# Power_Sheet.net
KiCad netlist of a schematic drawn in Altium Designer
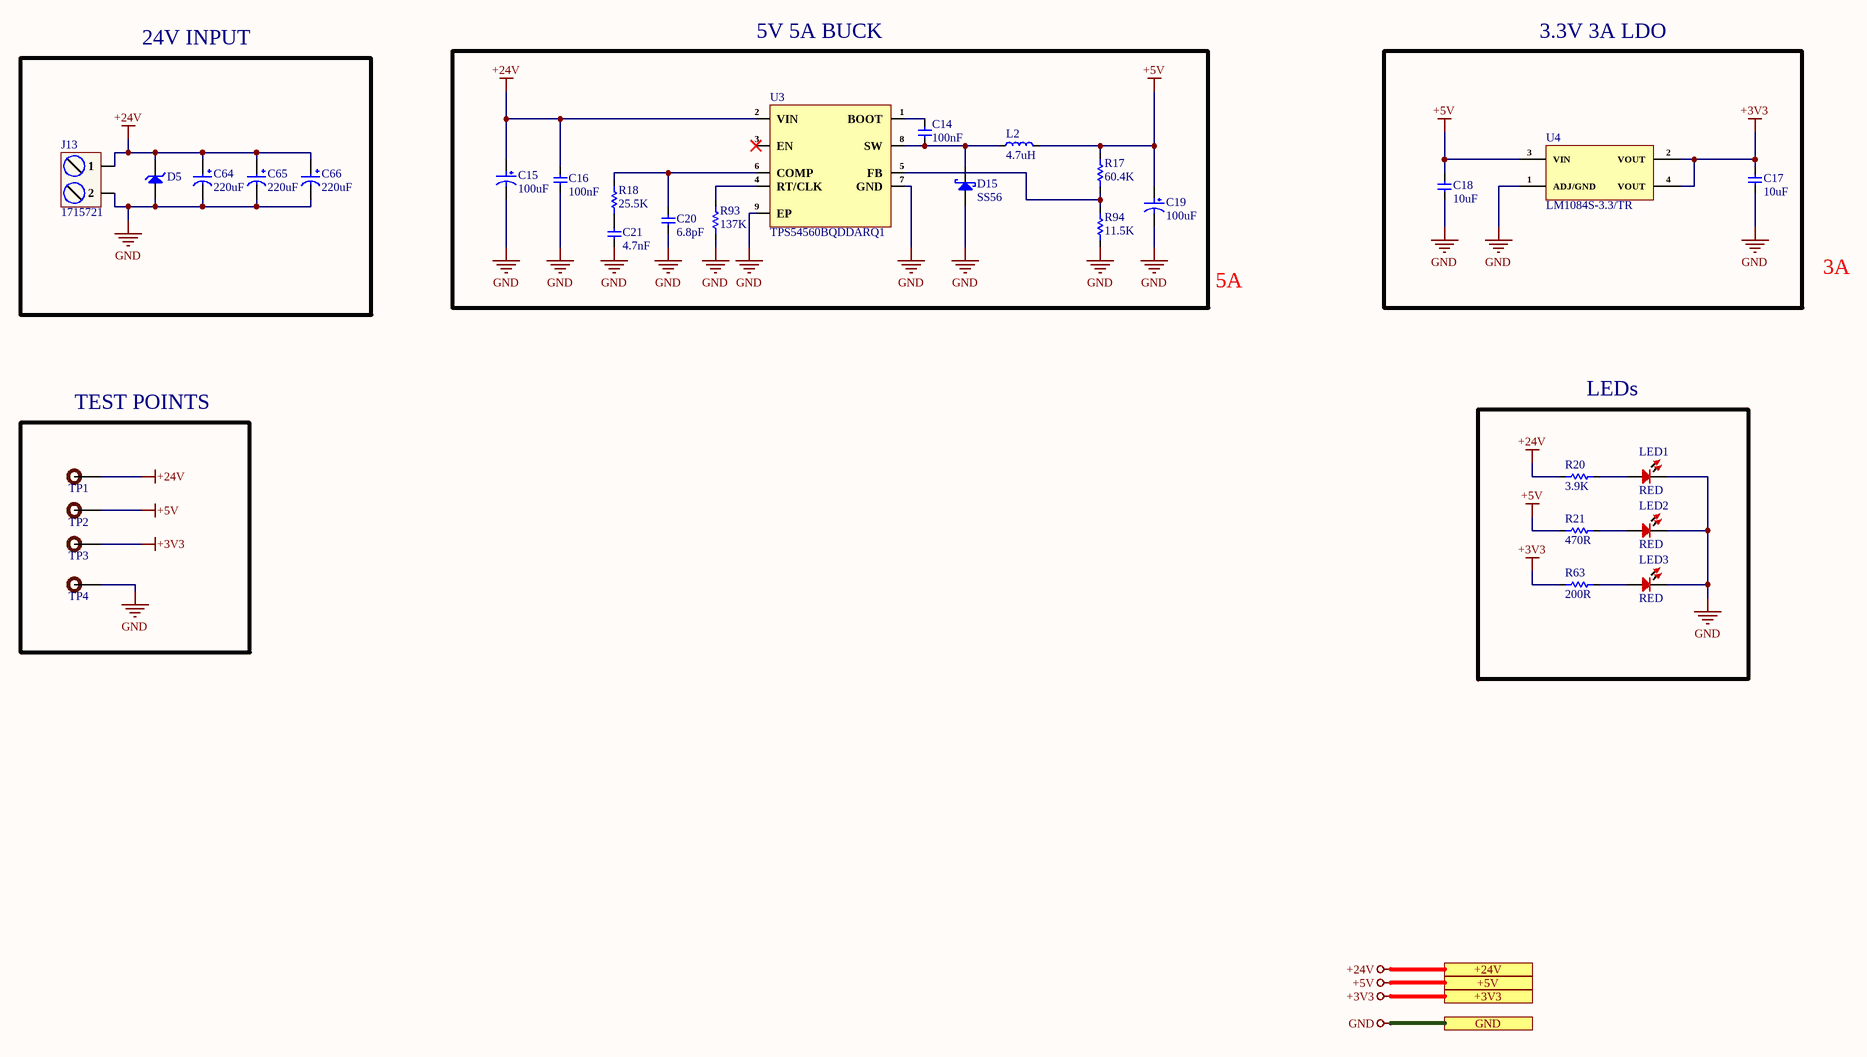
[diagram p0: Power_Sheet.SchDoc]

(export (version "E")
  (design (tool "Eeschema 10.0.6"))
  (components
    (comp (ref "C14")
      (value "100nF")
      (footprint "cap-0402")
      (description "CAP CER 0.1UF 50V X7R 0402")
      (fields
        (field (name "MANUFACTURER") "TDK")
        (field (name "MANUFACTURER PART NUMBER") "C1005X7R1H104KT000F")
      )
      (libsource (lib "eSpark Libraries") (part "C1005X7R1H104KT000F"))
    )
    (comp (ref "C15")
      (value "100uF")
      (footprint "RVT1A101M0605")
      (description "100uF 10V 55mA@120Hz ±20% SMD,D6.3xL5.4mm Aluminum Electrolytic Capacitors - SMD ROHS")
      (fields
        (field (name "MANUFACTURER") "ROQANG")
        (field (name "MANUFACTURER PART NUMBER") "RVT1A101M0605")
      )
      (libsource (lib "eSpark Libraries") (part "RVT1A101M0605"))
    )
    (comp (ref "C16")
      (value "100nF")
      (footprint "cap-0402")
      (description "CAP CER 0.1UF 50V X7R 0402")
      (fields
        (field (name "MANUFACTURER") "TDK")
        (field (name "MANUFACTURER PART NUMBER") "C1005X7R1H104KT000F")
      )
      (libsource (lib "eSpark Libraries") (part "C1005X7R1H104KT000F"))
    )
    (comp (ref "C17")
      (value "10uF")
      (footprint "Cap-0603")
      (description "CAP CER 10UF 25V X5R 0603")
      (fields
        (field (name "MANUFACTURER") "TDK")
        (field (name "MANUFACTURER PART NUMBER") "C1608X5R1E106M080AC")
      )
      (libsource (lib "eSpark Libraries") (part "C1608X5R1E106M080AC"))
    )
    (comp (ref "C18")
      (value "10uF")
      (footprint "Cap-0603")
      (description "CAP CER 10UF 25V X5R 0603")
      (fields
        (field (name "MANUFACTURER") "TDK")
        (field (name "MANUFACTURER PART NUMBER") "C1608X5R1E106M080AC")
      )
      (libsource (lib "eSpark Libraries") (part "C1608X5R1E106M080AC"))
    )
    (comp (ref "C19")
      (value "100uF")
      (footprint "RVT1A101M0605")
      (description "100uF 10V 55mA@120Hz ±20% SMD,D6.3xL5.4mm Aluminum Electrolytic Capacitors - SMD ROHS")
      (fields
        (field (name "MANUFACTURER") "ROQANG")
        (field (name "MANUFACTURER PART NUMBER") "RVT1A101M0605")
      )
      (libsource (lib "eSpark Libraries") (part "RVT1A101M0605"))
    )
    (comp (ref "C20")
      (value "6.8pF")
      (footprint "Cap-0402")
      (description "CAP CER 6.8PF 50V C0G/NPO 0402")
      (fields
        (field (name "MANUFACTURER") "Yageo")
        (field (name "MANUFACTURER PART NUMBER") "CC0402CRNPO9BN6R8")
      )
      (libsource (lib "eSpark Libraries") (part "CC0402CRNPO9BN6R8"))
    )
    (comp (ref "C21")
      (value "4.7nF")
      (footprint "Cap-0402")
      (description "CAP CER 4700PF 50V X7R 0402")
      (fields
        (field (name "MANUFACTURER") "Yageo")
        (field (name "MANUFACTURER PART NUMBER") "CC0402KRX7R9BB472")
      )
      (libsource (lib "eSpark Libraries") (part "CC0402KRX7R9BB472"))
    )
    (comp (ref "C64")
      (value "220uF")
      (footprint "UCD-220uF-10mmDia")
      (description "CAP ALUM 220UF 20% 50V SMD")
      (fields
        (field (name "MANUFACTURER") "Nichicon")
        (field (name "MANUFACTURER PART NUMBER") "UCD1H221MNL1GS")
      )
      (libsource (lib "eSpark Libraries") (part "UCD1H221MNL1GS"))
    )
    (comp (ref "C65")
      (value "220uF")
      (footprint "UCD-220uF-10mmDia")
      (description "CAP ALUM 220UF 20% 50V SMD")
      (fields
        (field (name "MANUFACTURER") "Nichicon")
        (field (name "MANUFACTURER PART NUMBER") "UCD1H221MNL1GS")
      )
      (libsource (lib "eSpark Libraries") (part "UCD1H221MNL1GS"))
    )
    (comp (ref "C66")
      (value "220uF")
      (footprint "UCD-220uF-10mmDia")
      (description "CAP ALUM 220UF 20% 50V SMD")
      (fields
        (field (name "MANUFACTURER") "Nichicon")
        (field (name "MANUFACTURER PART NUMBER") "UCD1H221MNL1GS")
      )
      (libsource (lib "eSpark Libraries") (part "UCD1H221MNL1GS"))
    )
    (comp (ref "D5")
      (value "SMBJ28A-13-F")
      (footprint "SMB_")
      (description "TVS DIODE 28VWM 45.4VC SMB")
      (fields (field (name "MANUFACTURER") "Diodes"))
      (libsource (lib "eSpark Libraries") (part "SMBJ28A-13-F"))
    )
    (comp (ref "D15")
      (value "SS56")
      (footprint "SMA")
      (description "DIODE SCHOTTKY 60V 5A SMA")
      (fields (field (name "MANUFACTURER") "MDD"))
      (libsource (lib "eSpark Libraries") (part "SS56"))
    )
    (comp (ref "J13")
      (value "1715721")
      (footprint "1715721")
      (description "TERM BLK 2P SIDE ENT 5.08MM PCB")
      (fields (field (name "MANUFACTURER") "Phoenix Contact"))
      (libsource (lib "eSpark Libraries") (part "1715721"))
    )
    (comp (ref "L2")
      (value "4.7uH")
      (footprint "YSPI1050-4R7M")
      (description "8A 4.7uH ±20% SMD,10x10.1mm Power Inductors ROHS")
      (fields
        (field (name "MANUFACTURER") "YJYCOIN")
        (field (name "MANUFACTURER PART NUMBER") "YSPI1050-4R7M")
      )
      (libsource (lib "eSpark Libraries") (part "YSPI1050-4R7M"))
    )
    (comp (ref "LED1")
      (value "RED")
      (footprint "LED-0603")
      (description "RED LED 0603 Light Emitting Diodes")
      (fields
        (field (name "MANUFACTURER") "Foshan NationStar Optoelectronics")
        (field (name "MANUFACTURER PART NUMBER") "NCD0603R3")
      )
      (libsource (lib "eSpark Libraries") (part "NCD0603R3"))
    )
    (comp (ref "LED2")
      (value "RED")
      (footprint "LED-0603")
      (description "RED LED 0603 Light Emitting Diodes")
      (fields
        (field (name "MANUFACTURER") "Foshan NationStar Optoelectronics")
        (field (name "MANUFACTURER PART NUMBER") "NCD0603R3")
      )
      (libsource (lib "eSpark Libraries") (part "NCD0603R3"))
    )
    (comp (ref "LED3")
      (value "RED")
      (footprint "LED-0603")
      (description "RED LED 0603 Light Emitting Diodes")
      (fields
        (field (name "MANUFACTURER") "Foshan NationStar Optoelectronics")
        (field (name "MANUFACTURER PART NUMBER") "NCD0603R3")
      )
      (libsource (lib "eSpark Libraries") (part "NCD0603R3"))
    )
    (comp (ref "R17")
      (value "60.4K")
      (footprint "Res-0402")
      (description "60.4kΩ 50V 62.5mW Thick Film Resistors ±1% 0402 Chip Resistor - Surface Mount ROHS")
      (fields (field (name "MANUFACTURER") "VO") (field (name "MANUFACTURER PART NUMBER") "SCR0402F60K4"))
      (libsource (lib "eSpark Libraries") (part "SCR0402F60K4"))
    )
    (comp (ref "R18")
      (value "25.5K")
      (footprint "Res-0402")
      (description "62.5mW Thick Film Resistors 50V ±100ppm/℃ ±1% 25.5kΩ 0402 Chip Resistor - Surface Mount ROHS")
      (fields
        (field (name "LCSC PART NUMBER") "C26970")
        (field (name "MANUFACTURER") "Royal Electronic Factory")
      )
      (libsource (lib "eSpark Libraries") (part "0402WGF2552TCE"))
    )
    (comp (ref "R20")
      (value "3.9K")
      (footprint "Res-0402")
      (description "RES 3.9K OHM 1% 1/16W 0402")
      (fields
        (field (name "MANUFACTURER") "Yageo")
        (field (name "MANUFACTURER PART NUMBER") "RC0402FR-073K9L")
      )
      (libsource (lib "eSpark Libraries") (part "RC0402FR-073K9L"))
    )
    (comp (ref "R21")
      (value "470R")
      (footprint "Res-0402")
      (description "RES 470 OHM 1% 1/16W 0402")
      (fields
        (field (name "MANUFACTURER") "Yageo")
        (field (name "MANUFACTURER PART NUMBER") "RC0402FR-07470RL")
      )
      (libsource (lib "eSpark Libraries") (part "RC0402FR-07470RL"))
    )
    (comp (ref "R63")
      (value "200R")
      (footprint "Res-0402")
      (description "RES 200 OHM 1% 1/16W 0402")
      (fields
        (field (name "MANUFACTURER") "Yageo")
        (field (name "MANUFACTURER PART NUMBER") "RC0402FR-07200RL")
      )
      (libsource (lib "eSpark Libraries") (part "RC0402FR-07200RL"))
    )
    (comp (ref "R93")
      (value "137K")
      (footprint "Res-0402")
      (description "RES SMD 137K OHM 0.1% 1/16W 0402")
      (fields (field (name "LCSC PART NUMBER") "C852519") (field (name "MANUFACTURER") "Yageo"))
      (libsource (lib "eSpark Libraries") (part "RT0402BRD07137KL"))
    )
    (comp (ref "R94")
      (value "11.5K")
      (footprint "Res-0402")
      (description "11.5kΩ 50V 62.5mW Thick Film Resistors ±100ppm/℃ ±1%  0402 Chip Resistor - Surface Mount ROHS")
      (fields
        (field (name "MANUFACTURER") "FOJAN")
        (field (name "MANUFACTURER PART NUMBER") "FRC0402F1152TS")
      )
      (libsource (lib "eSpark Libraries") (part "FRC0402F1152TS"))
    )
    (comp (ref "TP1")
      (value "TEST POINT")
      (footprint "Test-point")
      (description "Test Point ON")
      (libsource (lib "eSpark Libraries") (part "TEST POINT"))
    )
    (comp (ref "TP2")
      (value "TEST POINT")
      (footprint "Test-point")
      (description "Test Point ON")
      (libsource (lib "eSpark Libraries") (part "TEST POINT"))
    )
    (comp (ref "TP3")
      (value "TEST POINT")
      (footprint "Test-point")
      (description "Test Point ON")
      (libsource (lib "eSpark Libraries") (part "TEST POINT"))
    )
    (comp (ref "TP4")
      (value "TEST POINT")
      (footprint "Test-point")
      (description "Test Point ON")
      (libsource (lib "eSpark Libraries") (part "TEST POINT"))
    )
    (comp (ref "U3")
      (value "TPS54560BQDDARQ1")
      (footprint "8-SO PowerPad")
      (description "IC REG BCK SPLIT RAIL ADJ 8SOPWR")
      (fields (field (name "MANUFACTURER") "Texas Instruments") (field (name "LCSC PART NUMBER") "C2072188"))
      (libsource (lib "eSpark Libraries") (part "TPS54560BQDDARQ1"))
    )
    (comp (ref "U4")
      (value "LM1084S-3.3/TR")
      (footprint "TO263-3_")
      (description "72dB@(120Hz) 5A Fixed 3.3V~3.3V Positive 12V TO-263-3 Linear Voltage Regulators (LDO) ROHS")
      (fields (field (name "MANUFACTURER") "HGSEMI") (field (name "LCSC PART NUMBER") "C259972"))
      (libsource (lib "eSpark Libraries") (part "LM1084S-3.3/TR"))
    )
  )
  (nets
    (net (code "1") (name "+3V3") (class "Default")
      (node (ref "C17") (pin "2") (pinfunction "2_2") (pintype "passive"))
      (node (ref "R63") (pin "1") (pinfunction "1_1") (pintype "passive"))
      (node (ref "TP3") (pin "1") (pinfunction "1_1") (pintype "passive"))
      (node (ref "U4") (pin "2") (pinfunction "VOUT_2") (pintype "passive"))
      (node (ref "U4") (pin "4") (pinfunction "VOUT_4") (pintype "passive"))
    )
    (net (code "2") (name "+5V") (class "Default")
      (node (ref "C18") (pin "2") (pinfunction "2_2") (pintype "passive"))
      (node (ref "C19") (pin "1") (pintype "passive"))
      (node (ref "L2") (pin "2") (pinfunction "2_2") (pintype "passive"))
      (node (ref "R17") (pin "2") (pinfunction "2_2") (pintype "passive"))
      (node (ref "R21") (pin "1") (pinfunction "1_1") (pintype "passive"))
      (node (ref "TP2") (pin "1") (pinfunction "1_1") (pintype "passive"))
      (node (ref "U4") (pin "3") (pinfunction "VIN_3") (pintype "passive"))
    )
    (net (code "3") (name "+24V") (class "Default")
      (node (ref "C15") (pin "1") (pintype "passive"))
      (node (ref "C16") (pin "2") (pinfunction "2_2") (pintype "passive"))
      (node (ref "C64") (pin "1") (pinfunction "1_1") (pintype "passive"))
      (node (ref "C65") (pin "1") (pinfunction "1_1") (pintype "passive"))
      (node (ref "C66") (pin "1") (pinfunction "1_1") (pintype "passive"))
      (node (ref "D5") (pin "2") (pinfunction "K_2") (pintype "passive"))
      (node (ref "J13") (pin "1") (pinfunction "1_1") (pintype "passive"))
      (node (ref "R20") (pin "1") (pinfunction "1_1") (pintype "passive"))
      (node (ref "TP1") (pin "1") (pinfunction "1_1") (pintype "passive"))
      (node (ref "U3") (pin "2") (pinfunction "VIN_2") (pintype "passive"))
    )
    (net (code "4") (name "GND") (class "Default")
      (node (ref "C15") (pin "2") (pintype "passive"))
      (node (ref "C16") (pin "1") (pinfunction "1_1") (pintype "passive"))
      (node (ref "C17") (pin "1") (pinfunction "1_1") (pintype "passive"))
      (node (ref "C18") (pin "1") (pinfunction "1_1") (pintype "passive"))
      (node (ref "C19") (pin "2") (pintype "passive"))
      (node (ref "C20") (pin "1") (pinfunction "1_1") (pintype "passive"))
      (node (ref "C21") (pin "1") (pinfunction "1_1") (pintype "passive"))
      (node (ref "C64") (pin "2") (pinfunction "2_2") (pintype "passive"))
      (node (ref "C65") (pin "2") (pinfunction "2_2") (pintype "passive"))
      (node (ref "C66") (pin "2") (pinfunction "2_2") (pintype "passive"))
      (node (ref "D15") (pin "2") (pinfunction "A_2") (pintype "passive"))
      (node (ref "D5") (pin "1") (pinfunction "A_1") (pintype "passive"))
      (node (ref "J13") (pin "2") (pinfunction "2_2") (pintype "passive"))
      (node (ref "LED1") (pin "2") (pinfunction "2_2") (pintype "passive"))
      (node (ref "LED2") (pin "2") (pinfunction "2_2") (pintype "passive"))
      (node (ref "LED3") (pin "2") (pinfunction "2_2") (pintype "passive"))
      (node (ref "R93") (pin "1") (pinfunction "1_1") (pintype "passive"))
      (node (ref "R94") (pin "1") (pinfunction "1_1") (pintype "passive"))
      (node (ref "TP4") (pin "1") (pinfunction "1_1") (pintype "passive"))
      (node (ref "U3") (pin "7") (pinfunction "GND_7") (pintype "passive"))
      (node (ref "U3") (pin "9") (pinfunction "EP_9") (pintype "passive"))
      (node (ref "U4") (pin "1") (pinfunction "ADJ/GND_1") (pintype "passive"))
    )
    (net (code "5") (name "Net-(C21-Pad2)") (class "Default")
      (node (ref "C21") (pin "2") (pinfunction "2_2") (pintype "passive"))
      (node (ref "R18") (pin "1") (pinfunction "1_1") (pintype "passive"))
    )
    (net (code "6") (name "Net-(D15-K)") (class "Default")
      (node (ref "C14") (pin "1") (pinfunction "1_1") (pintype "passive"))
      (node (ref "D15") (pin "1") (pinfunction "K_1") (pintype "passive"))
      (node (ref "L2") (pin "1") (pinfunction "1_1") (pintype "passive"))
      (node (ref "U3") (pin "8") (pinfunction "SW_8") (pintype "passive"))
    )
    (net (code "7") (name "Net-(LED1-Pad1)") (class "Default")
      (node (ref "LED1") (pin "1") (pinfunction "1_1") (pintype "passive"))
      (node (ref "R20") (pin "2") (pinfunction "2_2") (pintype "passive"))
    )
    (net (code "8") (name "Net-(LED2-Pad1)") (class "Default")
      (node (ref "LED2") (pin "1") (pinfunction "1_1") (pintype "passive"))
      (node (ref "R21") (pin "2") (pinfunction "2_2") (pintype "passive"))
    )
    (net (code "9") (name "Net-(LED3-Pad1)") (class "Default")
      (node (ref "LED3") (pin "1") (pinfunction "1_1") (pintype "passive"))
      (node (ref "R63") (pin "2") (pinfunction "2_2") (pintype "passive"))
    )
    (net (code "10") (name "Net-(U3-BOOT)") (class "Default")
      (node (ref "C14") (pin "2") (pinfunction "2_2") (pintype "passive"))
      (node (ref "U3") (pin "1") (pinfunction "BOOT_1") (pintype "passive"))
    )
    (net (code "11") (name "Net-(U3-COMP)") (class "Default")
      (node (ref "C20") (pin "2") (pinfunction "2_2") (pintype "passive"))
      (node (ref "R18") (pin "2") (pinfunction "2_2") (pintype "passive"))
      (node (ref "U3") (pin "6") (pinfunction "COMP_6") (pintype "passive"))
    )
    (net (code "12") (name "Net-(U3-FB)") (class "Default")
      (node (ref "R17") (pin "1") (pinfunction "1_1") (pintype "passive"))
      (node (ref "R94") (pin "2") (pinfunction "2_2") (pintype "passive"))
      (node (ref "U3") (pin "5") (pinfunction "FB_5") (pintype "passive"))
    )
    (net (code "13") (name "Net-(U3-RT{slash}CLK)") (class "Default")
      (node (ref "R93") (pin "2") (pinfunction "2_2") (pintype "passive"))
      (node (ref "U3") (pin "4") (pinfunction "RT/CLK_4") (pintype "passive"))
    )
    (net (code "14") (name "unconnected-(U3-EN-Pad3)") (class "Default")
      (node (ref "U3") (pin "3") (pinfunction "EN_3") (pintype "passive+no_connect"))
    )
  )
)
